# Remote_Control.net
KiCad netlist of a schematic drawn in Altium Designer
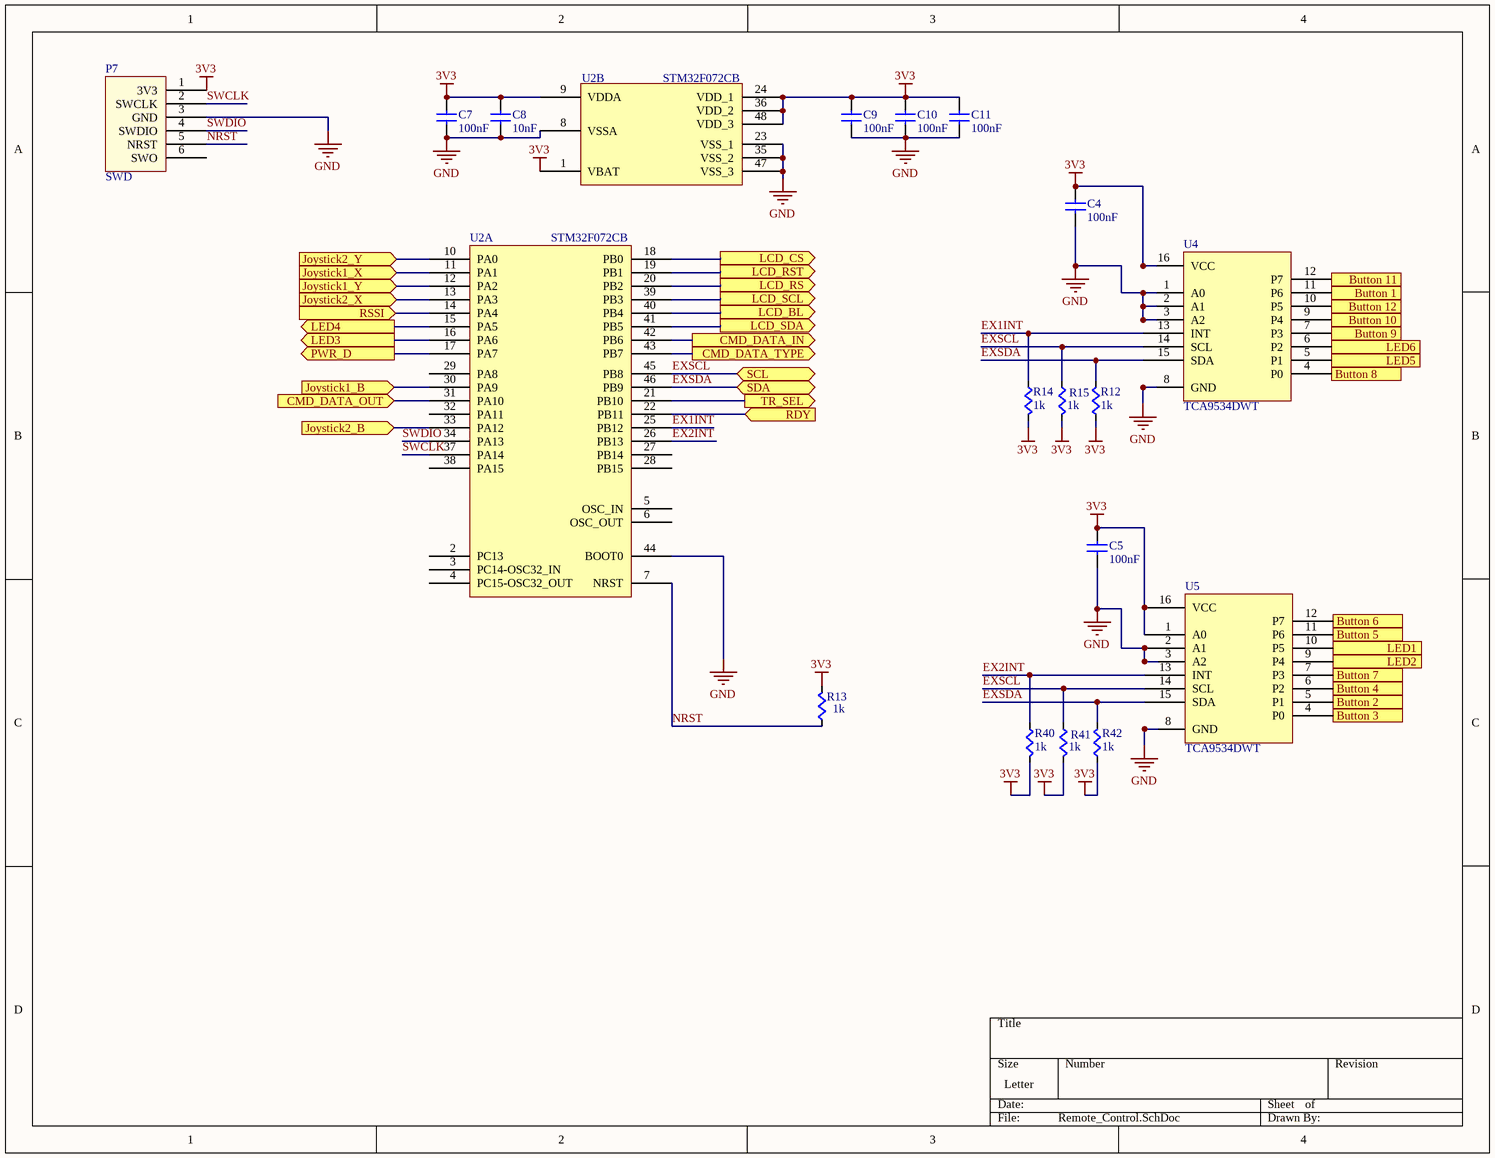
[diagram p0: Remote_Control.SchDoc]

(export (version "E")
  (design (tool "Eeschema 10.0.6"))
  (components
    (comp (ref "C4")
      (value "100nF")
      (footprint "CAPC0603")
      (fields (field (name "Comment") "Cap"))
      (libsource (lib "SubjuGator8") (part "Cap"))
    )
    (comp (ref "C5")
      (value "100nF")
      (footprint "CAPC0603")
      (fields (field (name "Comment") "Cap"))
      (libsource (lib "SubjuGator8") (part "Cap"))
    )
    (comp (ref "C7")
      (value "100nF")
      (footprint "CAPC0603")
      (fields (field (name "Comment") "Cap"))
      (libsource (lib "SubjuGator8") (part "Cap"))
    )
    (comp (ref "C8")
      (value "10nF")
      (footprint "CAPC0603")
      (fields (field (name "Comment") "Cap"))
      (libsource (lib "SubjuGator8") (part "Cap"))
    )
    (comp (ref "C9")
      (value "100nF")
      (footprint "CAPC0603")
      (fields (field (name "Comment") "Cap"))
      (libsource (lib "SubjuGator8") (part "Cap"))
    )
    (comp (ref "C10")
      (value "100nF")
      (footprint "CAPC0603")
      (fields (field (name "Comment") "Cap"))
      (libsource (lib "SubjuGator8") (part "Cap"))
    )
    (comp (ref "C11")
      (value "100nF")
      (footprint "CAPC0603")
      (fields (field (name "Comment") "Cap"))
      (libsource (lib "SubjuGator8") (part "Cap"))
    )
    (comp (ref "P7")
      (value "SWD")
      (footprint "SWD_STM32")
      (description "SWD connector matching the pinout on STM Discovery Boards")
      (libsource (lib "SubjuGator8") (part "SWD_STM32"))
    )
    (comp (ref "R12")
      (value "1k")
      (footprint "RES0603")
      (fields (field (name "Comment") "Res"))
      (libsource (lib "SubjuGator8") (part "Res"))
    )
    (comp (ref "R13")
      (value "1k")
      (footprint "RES0603")
      (fields (field (name "Comment") "Res"))
      (libsource (lib "SubjuGator8") (part "Res"))
    )
    (comp (ref "R14")
      (value "1k")
      (footprint "RES0603")
      (fields (field (name "Comment") "Res"))
      (libsource (lib "SubjuGator8") (part "Res"))
    )
    (comp (ref "R15")
      (value "1k")
      (footprint "RES0603")
      (fields (field (name "Comment") "Res"))
      (libsource (lib "SubjuGator8") (part "Res"))
    )
    (comp (ref "R40")
      (value "1k")
      (footprint "RES0603")
      (fields (field (name "Comment") "Res"))
      (libsource (lib "SubjuGator8") (part "Res"))
    )
    (comp (ref "R41")
      (value "1k")
      (footprint "RES0603")
      (fields (field (name "Comment") "Res"))
      (libsource (lib "SubjuGator8") (part "Res"))
    )
    (comp (ref "R42")
      (value "1k")
      (footprint "RES0603")
      (fields (field (name "Comment") "Res"))
      (libsource (lib "SubjuGator8") (part "Res"))
    )
    (comp (ref "U2")
      (value "STM32F072CB")
      (footprint "STM32F072CB")
      (description "MCU 32BIT 128KB FLASH 48LQFP")
      (libsource (lib "SubjuGator8") (part "STM32F072CB"))
    )
    (comp (ref "U4")
      (value "TCA9534DWT")
      (footprint "TCA9534DWT")
      (description "IC I/O EXPANDER I2C 8B 16-SOIC")
      (libsource (lib "SubjuGator8") (part "TCA9534DWT"))
    )
    (comp (ref "U5")
      (value "TCA9534DWT")
      (footprint "TCA9534DWT")
      (description "IC I/O EXPANDER I2C 8B 16-SOIC")
      (libsource (lib "SubjuGator8") (part "TCA9534DWT"))
    )
  )
  (nets
    (net (code "1") (name "/Button 1") (class "Default")
      (node (ref "U4") (pin "11") (pinfunction "P6_11") (pintype "passive"))
    )
    (net (code "2") (name "/Button 2") (class "Default")
      (node (ref "U5") (pin "5") (pinfunction "P1_5") (pintype "passive"))
    )
    (net (code "3") (name "/Button 3") (class "Default")
      (node (ref "U5") (pin "4") (pinfunction "P0_4") (pintype "passive"))
    )
    (net (code "4") (name "/Button 4") (class "Default")
      (node (ref "U5") (pin "6") (pinfunction "P2_6") (pintype "passive"))
    )
    (net (code "5") (name "/Button 5") (class "Default")
      (node (ref "U5") (pin "11") (pinfunction "P6_11") (pintype "passive"))
    )
    (net (code "6") (name "/Button 6") (class "Default")
      (node (ref "U5") (pin "12") (pinfunction "P7_12") (pintype "passive"))
    )
    (net (code "7") (name "/Button 7") (class "Default")
      (node (ref "U5") (pin "7") (pinfunction "P3_7") (pintype "passive"))
    )
    (net (code "8") (name "/Button 8") (class "Default")
      (node (ref "U4") (pin "4") (pinfunction "P0_4") (pintype "passive"))
    )
    (net (code "9") (name "/Button 9") (class "Default")
      (node (ref "U4") (pin "7") (pinfunction "P3_7") (pintype "passive"))
    )
    (net (code "10") (name "/Button 10") (class "Default")
      (node (ref "U4") (pin "9") (pinfunction "P4_9") (pintype "passive"))
    )
    (net (code "11") (name "/Button 11") (class "Default")
      (node (ref "U4") (pin "12") (pinfunction "P7_12") (pintype "passive"))
    )
    (net (code "12") (name "/Button 12") (class "Default")
      (node (ref "U4") (pin "10") (pinfunction "P5_10") (pintype "passive"))
    )
    (net (code "13") (name "/CMD_DATA_IN") (class "Default")
      (node (ref "U2") (pin "42") (pinfunction "PB6_42") (pintype "passive"))
    )
    (net (code "14") (name "/CMD_DATA_OUT") (class "Default")
      (node (ref "U2") (pin "31") (pinfunction "PA10_31") (pintype "passive"))
    )
    (net (code "15") (name "/CMD_DATA_TYPE") (class "Default")
      (node (ref "U2") (pin "43") (pinfunction "PB7_43") (pintype "passive"))
    )
    (net (code "16") (name "/EX1INT") (class "Default")
      (node (ref "R14") (pin "2") (pinfunction "B_2") (pintype "passive"))
      (node (ref "U2") (pin "25") (pinfunction "PB12_25") (pintype "passive"))
      (node (ref "U4") (pin "13") (pinfunction "INT_13") (pintype "passive"))
    )
    (net (code "17") (name "/EX2INT") (class "Default")
      (node (ref "R40") (pin "2") (pinfunction "B_2") (pintype "passive"))
      (node (ref "U2") (pin "26") (pinfunction "PB13_26") (pintype "passive"))
      (node (ref "U5") (pin "13") (pinfunction "INT_13") (pintype "passive"))
    )
    (net (code "18") (name "/EXSCL") (class "Default")
      (node (ref "R15") (pin "2") (pinfunction "B_2") (pintype "passive"))
      (node (ref "R41") (pin "2") (pinfunction "B_2") (pintype "passive"))
      (node (ref "U2") (pin "45") (pinfunction "PB8_45") (pintype "passive"))
      (node (ref "U4") (pin "14") (pinfunction "SCL_14") (pintype "passive"))
      (node (ref "U5") (pin "14") (pinfunction "SCL_14") (pintype "passive"))
    )
    (net (code "19") (name "/EXSDA") (class "Default")
      (node (ref "R12") (pin "1") (pinfunction "A_1") (pintype "passive"))
      (node (ref "R42") (pin "1") (pinfunction "A_1") (pintype "passive"))
      (node (ref "U2") (pin "46") (pinfunction "PB9_46") (pintype "passive"))
      (node (ref "U4") (pin "15") (pinfunction "SDA_15") (pintype "passive"))
      (node (ref "U5") (pin "15") (pinfunction "SDA_15") (pintype "passive"))
    )
    (net (code "20") (name "/Joystick1_B") (class "Default")
      (node (ref "U2") (pin "30") (pinfunction "PA9_30") (pintype "passive"))
    )
    (net (code "21") (name "/Joystick1_X") (class "Default")
      (node (ref "U2") (pin "11") (pinfunction "PA1_11") (pintype "passive"))
    )
    (net (code "22") (name "/Joystick1_Y") (class "Default")
      (node (ref "U2") (pin "12") (pinfunction "PA2_12") (pintype "passive"))
    )
    (net (code "23") (name "/Joystick2_B") (class "Default")
      (node (ref "U2") (pin "33") (pinfunction "PA12_33") (pintype "passive"))
    )
    (net (code "24") (name "/Joystick2_X") (class "Default")
      (node (ref "U2") (pin "13") (pinfunction "PA3_13") (pintype "passive"))
    )
    (net (code "25") (name "/Joystick2_Y") (class "Default")
      (node (ref "U2") (pin "10") (pinfunction "PA0_10") (pintype "passive"))
    )
    (net (code "26") (name "/LCD_BL") (class "Default")
      (node (ref "U2") (pin "40") (pinfunction "PB4_40") (pintype "passive"))
    )
    (net (code "27") (name "/LCD_CS") (class "Default")
      (node (ref "U2") (pin "18") (pinfunction "PB0_18") (pintype "passive"))
    )
    (net (code "28") (name "/LCD_RS") (class "Default")
      (node (ref "U2") (pin "20") (pinfunction "PB2_20") (pintype "passive"))
    )
    (net (code "29") (name "/LCD_RST") (class "Default")
      (node (ref "U2") (pin "19") (pinfunction "PB1_19") (pintype "passive"))
    )
    (net (code "30") (name "/LCD_SCL") (class "Default")
      (node (ref "U2") (pin "39") (pinfunction "PB3_39") (pintype "passive"))
    )
    (net (code "31") (name "/LCD_SDA") (class "Default")
      (node (ref "U2") (pin "41") (pinfunction "PB5_41") (pintype "passive"))
    )
    (net (code "32") (name "/LED1") (class "Default")
      (node (ref "U5") (pin "10") (pinfunction "P5_10") (pintype "passive"))
    )
    (net (code "33") (name "/LED2") (class "Default")
      (node (ref "U5") (pin "9") (pinfunction "P4_9") (pintype "passive"))
    )
    (net (code "34") (name "/LED3") (class "Default")
      (node (ref "U2") (pin "16") (pinfunction "PA6_16") (pintype "passive"))
    )
    (net (code "35") (name "/LED4") (class "Default")
      (node (ref "U2") (pin "15") (pinfunction "PA5_15") (pintype "passive"))
    )
    (net (code "36") (name "/LED5") (class "Default")
      (node (ref "U4") (pin "5") (pinfunction "P1_5") (pintype "passive"))
    )
    (net (code "37") (name "/LED6") (class "Default")
      (node (ref "U4") (pin "6") (pinfunction "P2_6") (pintype "passive"))
    )
    (net (code "38") (name "/NRST") (class "Default")
      (node (ref "P7") (pin "5") (pinfunction "NRST_5") (pintype "passive"))
      (node (ref "R13") (pin "2") (pinfunction "B_2") (pintype "passive"))
      (node (ref "U2") (pin "7") (pinfunction "NRST_7") (pintype "passive"))
    )
    (net (code "39") (name "/PWR_D") (class "Default")
      (node (ref "U2") (pin "17") (pinfunction "PA7_17") (pintype "passive"))
    )
    (net (code "40") (name "/RDY") (class "Default")
      (node (ref "U2") (pin "22") (pinfunction "PB11_22") (pintype "passive"))
    )
    (net (code "41") (name "/RSSI") (class "Default")
      (node (ref "U2") (pin "14") (pinfunction "PA4_14") (pintype "passive"))
    )
    (net (code "42") (name "/SWCLK") (class "Default")
      (node (ref "P7") (pin "2") (pinfunction "SWCLK_2") (pintype "passive"))
      (node (ref "U2") (pin "37") (pinfunction "PA14_37") (pintype "passive"))
    )
    (net (code "43") (name "/SWDIO") (class "Default")
      (node (ref "P7") (pin "4") (pinfunction "SWDIO_4") (pintype "passive"))
      (node (ref "U2") (pin "34") (pinfunction "PA13_34") (pintype "passive"))
    )
    (net (code "44") (name "/TR_SEL") (class "Default")
      (node (ref "U2") (pin "21") (pinfunction "PB10_21") (pintype "passive"))
    )
    (net (code "45") (name "3V3") (class "Default")
      (node (ref "C10") (pin "1") (pinfunction "A_1") (pintype "passive"))
      (node (ref "C11") (pin "1") (pinfunction "A_1") (pintype "passive"))
      (node (ref "C4") (pin "1") (pinfunction "A_1") (pintype "passive"))
      (node (ref "C5") (pin "1") (pinfunction "A_1") (pintype "passive"))
      (node (ref "C7") (pin "1") (pinfunction "A_1") (pintype "passive"))
      (node (ref "C8") (pin "1") (pinfunction "A_1") (pintype "passive"))
      (node (ref "C9") (pin "1") (pinfunction "A_1") (pintype "passive"))
      (node (ref "P7") (pin "1") (pinfunction "3V3_1") (pintype "passive"))
      (node (ref "R12") (pin "2") (pinfunction "B_2") (pintype "passive"))
      (node (ref "R13") (pin "1") (pinfunction "A_1") (pintype "passive"))
      (node (ref "R14") (pin "1") (pinfunction "A_1") (pintype "passive"))
      (node (ref "R15") (pin "1") (pinfunction "A_1") (pintype "passive"))
      (node (ref "R40") (pin "1") (pinfunction "A_1") (pintype "passive"))
      (node (ref "R41") (pin "1") (pinfunction "A_1") (pintype "passive"))
      (node (ref "R42") (pin "2") (pinfunction "B_2") (pintype "passive"))
      (node (ref "U2") (pin "1") (pinfunction "VBAT_1") (pintype "passive"))
      (node (ref "U2") (pin "24") (pinfunction "VDD_1_24") (pintype "passive"))
      (node (ref "U2") (pin "36") (pinfunction "VDD_2_36") (pintype "passive"))
      (node (ref "U2") (pin "48") (pinfunction "VDD_3_48") (pintype "passive"))
      (node (ref "U2") (pin "9") (pinfunction "VDDA_9") (pintype "passive"))
      (node (ref "U4") (pin "16") (pinfunction "VCC_16") (pintype "passive"))
      (node (ref "U5") (pin "1") (pinfunction "A0_1") (pintype "passive"))
      (node (ref "U5") (pin "16") (pinfunction "VCC_16") (pintype "passive"))
    )
    (net (code "46") (name "GND") (class "Default")
      (node (ref "C10") (pin "2") (pinfunction "B_2") (pintype "passive"))
      (node (ref "C11") (pin "2") (pinfunction "B_2") (pintype "passive"))
      (node (ref "C4") (pin "2") (pinfunction "B_2") (pintype "passive"))
      (node (ref "C5") (pin "2") (pinfunction "B_2") (pintype "passive"))
      (node (ref "C7") (pin "2") (pinfunction "B_2") (pintype "passive"))
      (node (ref "C8") (pin "2") (pinfunction "B_2") (pintype "passive"))
      (node (ref "C9") (pin "2") (pinfunction "B_2") (pintype "passive"))
      (node (ref "P7") (pin "3") (pinfunction "GND_3") (pintype "passive"))
      (node (ref "U2") (pin "23") (pinfunction "VSS_1_23") (pintype "passive"))
      (node (ref "U2") (pin "35") (pinfunction "VSS_2_35") (pintype "passive"))
      (node (ref "U2") (pin "44") (pinfunction "BOOT0_44") (pintype "passive"))
      (node (ref "U2") (pin "47") (pinfunction "VSS_3_47") (pintype "passive"))
      (node (ref "U2") (pin "8") (pinfunction "VSSA_8") (pintype "passive"))
      (node (ref "U4") (pin "1") (pinfunction "A0_1") (pintype "passive"))
      (node (ref "U4") (pin "2") (pinfunction "A1_2") (pintype "passive"))
      (node (ref "U4") (pin "3") (pinfunction "A2_3") (pintype "passive"))
      (node (ref "U4") (pin "8") (pinfunction "GND_8") (pintype "passive"))
      (node (ref "U5") (pin "2") (pinfunction "A1_2") (pintype "passive"))
      (node (ref "U5") (pin "3") (pinfunction "A2_3") (pintype "passive"))
      (node (ref "U5") (pin "8") (pinfunction "GND_8") (pintype "passive"))
    )
    (net (code "47") (name "unconnected-(P7-SWO-Pad6)") (class "Default")
      (node (ref "P7") (pin "6") (pinfunction "SWO_6") (pintype "passive"))
    )
    (net (code "48") (name "unconnected-(U2A-OSC_IN-Pad5)") (class "Default")
      (node (ref "U2") (pin "5") (pinfunction "OSC_IN_5") (pintype "passive"))
    )
    (net (code "49") (name "unconnected-(U2A-OSC_OUT-Pad6)") (class "Default")
      (node (ref "U2") (pin "6") (pinfunction "OSC_OUT_6") (pintype "passive"))
    )
    (net (code "50") (name "unconnected-(U2A-PA8-Pad29)") (class "Default")
      (node (ref "U2") (pin "29") (pinfunction "PA8_29") (pintype "passive"))
    )
    (net (code "51") (name "unconnected-(U2A-PA11-Pad32)") (class "Default")
      (node (ref "U2") (pin "32") (pinfunction "PA11_32") (pintype "passive"))
    )
    (net (code "52") (name "unconnected-(U2A-PA15-Pad38)") (class "Default")
      (node (ref "U2") (pin "38") (pinfunction "PA15_38") (pintype "passive"))
    )
    (net (code "53") (name "unconnected-(U2A-PB14-Pad27)") (class "Default")
      (node (ref "U2") (pin "27") (pinfunction "PB14_27") (pintype "passive"))
    )
    (net (code "54") (name "unconnected-(U2A-PB15-Pad28)") (class "Default")
      (node (ref "U2") (pin "28") (pinfunction "PB15_28") (pintype "passive"))
    )
    (net (code "55") (name "unconnected-(U2A-PC13-Pad2)") (class "Default")
      (node (ref "U2") (pin "2") (pinfunction "PC13_2") (pintype "passive"))
    )
    (net (code "56") (name "unconnected-(U2A-PC14-OSC32_IN-Pad3)") (class "Default")
      (node (ref "U2") (pin "3") (pinfunction "PC14-OSC32_IN_3") (pintype "passive"))
    )
    (net (code "57") (name "unconnected-(U2A-PC15-OSC32_OUT-Pad4)") (class "Default")
      (node (ref "U2") (pin "4") (pinfunction "PC15-OSC32_OUT_4") (pintype "passive"))
    )
  )
)
